# labwiz-module_full_breakout.net
KiCad netlist of a schematic drawn in EAGLE
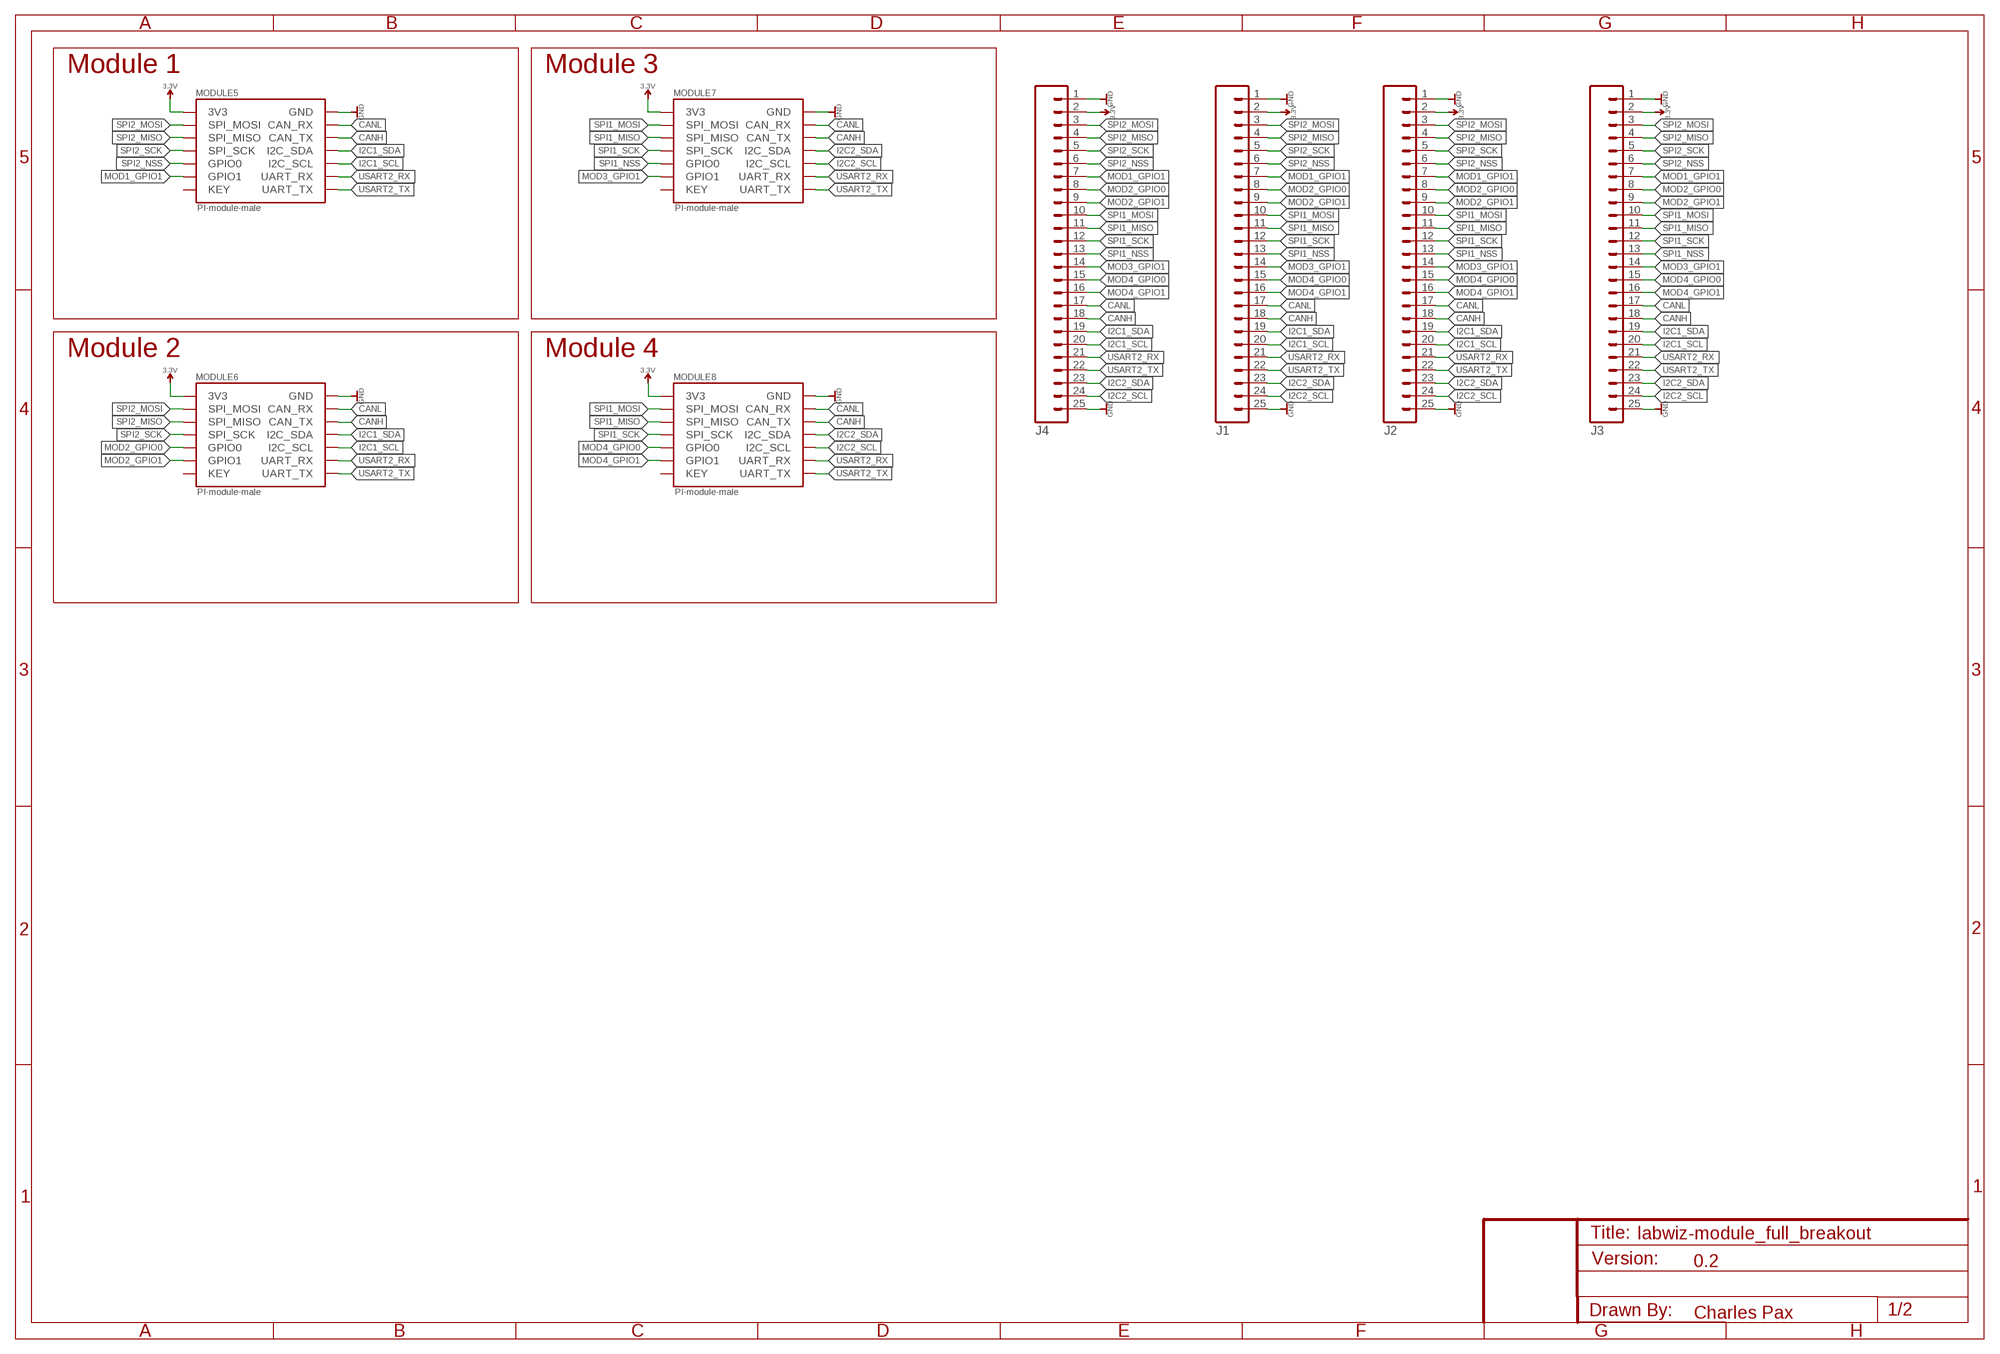
[diagram p0: schematic, sheet 1]

(export (version "E")
  (design (tool "Eeschema 10.0.6"))
  (components
    (comp (ref "J1")
      (value "M25PTH")
      (footprint "eagle-import:1X25")
      (libsource (lib "eagle-import") (part "M25PTH"))
    )
    (comp (ref "J2")
      (value "M25PTH")
      (footprint "eagle-import:1X25")
      (libsource (lib "eagle-import") (part "M25PTH"))
    )
    (comp (ref "J3")
      (value "M25PTH")
      (footprint "eagle-import:1X25")
      (libsource (lib "eagle-import") (part "M25PTH"))
    )
    (comp (ref "J4")
      (value "M25PTH")
      (footprint "eagle-import:1X25")
      (libsource (lib "eagle-import") (part "M25PTH"))
    )
    (comp (ref "MODULE5")
      (value "PI-module-male")
      (footprint "eagle-import:M07X2_2MM_EDGE")
      (fields (field (name "MF") "Pax Instruments") (field (name "MPN") "PIxxxx"))
      (libsource (lib "eagle-import") (part "PAX_MODULE_EDGE_MALE_MODULE"))
    )
    (comp (ref "MODULE6")
      (value "PI-module-male")
      (footprint "eagle-import:M07X2_2MM_EDGE")
      (fields (field (name "MF") "Pax Instruments") (field (name "MPN") "PIxxxx"))
      (libsource (lib "eagle-import") (part "PAX_MODULE_EDGE_MALE_MODULE"))
    )
    (comp (ref "MODULE7")
      (value "PI-module-male")
      (footprint "eagle-import:M07X2_2MM_EDGE")
      (fields (field (name "MF") "Pax Instruments") (field (name "MPN") "PIxxxx"))
      (libsource (lib "eagle-import") (part "PAX_MODULE_EDGE_MALE_MODULE"))
    )
    (comp (ref "MODULE8")
      (value "PI-module-male")
      (footprint "eagle-import:M07X2_2MM_EDGE")
      (fields (field (name "MF") "Pax Instruments") (field (name "MPN") "PIxxxx"))
      (libsource (lib "eagle-import") (part "PAX_MODULE_EDGE_MALE_MODULE"))
    )
  )
  (nets
    (net (code "1") (name "3.3V") (class "Default")
      (node (ref "J1") (pin "2") (pinfunction "2_2") (pintype "passive"))
      (node (ref "J2") (pin "2") (pinfunction "2_2") (pintype "passive"))
      (node (ref "J3") (pin "2") (pinfunction "2_2") (pintype "passive"))
      (node (ref "J4") (pin "2") (pinfunction "2_2") (pintype "passive"))
      (node (ref "MODULE5") (pin "P$13") (pinfunction "3V3_P$13") (pintype "power_in"))
      (node (ref "MODULE6") (pin "P$13") (pinfunction "3V3_P$13") (pintype "power_in"))
      (node (ref "MODULE7") (pin "P$13") (pinfunction "3V3_P$13") (pintype "power_in"))
      (node (ref "MODULE8") (pin "P$13") (pinfunction "3V3_P$13") (pintype "power_in"))
    )
    (net (code "2") (name "CANH") (class "Default")
      (node (ref "J1") (pin "18") (pinfunction "18_18") (pintype "passive"))
      (node (ref "J2") (pin "18") (pinfunction "18_18") (pintype "passive"))
      (node (ref "J3") (pin "18") (pinfunction "18_18") (pintype "passive"))
      (node (ref "J4") (pin "18") (pinfunction "18_18") (pintype "passive"))
      (node (ref "MODULE5") (pin "P$10") (pinfunction "CAN_TX_P$10") (pintype "bidirectional"))
      (node (ref "MODULE6") (pin "P$10") (pinfunction "CAN_TX_P$10") (pintype "bidirectional"))
      (node (ref "MODULE7") (pin "P$10") (pinfunction "CAN_TX_P$10") (pintype "bidirectional"))
      (node (ref "MODULE8") (pin "P$10") (pinfunction "CAN_TX_P$10") (pintype "bidirectional"))
    )
    (net (code "3") (name "CANL") (class "Default")
      (node (ref "J1") (pin "17") (pinfunction "17_17") (pintype "passive"))
      (node (ref "J2") (pin "17") (pinfunction "17_17") (pintype "passive"))
      (node (ref "J3") (pin "17") (pinfunction "17_17") (pintype "passive"))
      (node (ref "J4") (pin "17") (pinfunction "17_17") (pintype "passive"))
      (node (ref "MODULE5") (pin "P$12") (pinfunction "CAN_RX_P$12") (pintype "bidirectional"))
      (node (ref "MODULE6") (pin "P$12") (pinfunction "CAN_RX_P$12") (pintype "bidirectional"))
      (node (ref "MODULE7") (pin "P$12") (pinfunction "CAN_RX_P$12") (pintype "bidirectional"))
      (node (ref "MODULE8") (pin "P$12") (pinfunction "CAN_RX_P$12") (pintype "bidirectional"))
    )
    (net (code "4") (name "GND") (class "Default")
      (node (ref "J1") (pin "1") (pinfunction "1_1") (pintype "passive"))
      (node (ref "J1") (pin "25") (pinfunction "25_25") (pintype "passive"))
      (node (ref "J2") (pin "1") (pinfunction "1_1") (pintype "passive"))
      (node (ref "J2") (pin "25") (pinfunction "25_25") (pintype "passive"))
      (node (ref "J3") (pin "1") (pinfunction "1_1") (pintype "passive"))
      (node (ref "J3") (pin "25") (pinfunction "25_25") (pintype "passive"))
      (node (ref "J4") (pin "1") (pinfunction "1_1") (pintype "passive"))
      (node (ref "J4") (pin "25") (pinfunction "25_25") (pintype "passive"))
      (node (ref "MODULE5") (pin "P$14") (pinfunction "GND_P$14") (pintype "power_in"))
      (node (ref "MODULE6") (pin "P$14") (pinfunction "GND_P$14") (pintype "power_in"))
      (node (ref "MODULE7") (pin "P$14") (pinfunction "GND_P$14") (pintype "power_in"))
      (node (ref "MODULE8") (pin "P$14") (pinfunction "GND_P$14") (pintype "power_in"))
    )
    (net (code "5") (name "I2C1_SCL") (class "Default")
      (node (ref "J1") (pin "20") (pinfunction "20_20") (pintype "passive"))
      (node (ref "J2") (pin "20") (pinfunction "20_20") (pintype "passive"))
      (node (ref "J3") (pin "20") (pinfunction "20_20") (pintype "passive"))
      (node (ref "J4") (pin "20") (pinfunction "20_20") (pintype "passive"))
      (node (ref "MODULE5") (pin "P$6") (pinfunction "I2C_SCL_P$6") (pintype "bidirectional"))
      (node (ref "MODULE6") (pin "P$6") (pinfunction "I2C_SCL_P$6") (pintype "bidirectional"))
    )
    (net (code "6") (name "I2C1_SDA") (class "Default")
      (node (ref "J1") (pin "19") (pinfunction "19_19") (pintype "passive"))
      (node (ref "J2") (pin "19") (pinfunction "19_19") (pintype "passive"))
      (node (ref "J3") (pin "19") (pinfunction "19_19") (pintype "passive"))
      (node (ref "J4") (pin "19") (pinfunction "19_19") (pintype "passive"))
      (node (ref "MODULE5") (pin "P$8") (pinfunction "I2C_SDA_P$8") (pintype "bidirectional"))
      (node (ref "MODULE6") (pin "P$8") (pinfunction "I2C_SDA_P$8") (pintype "bidirectional"))
    )
    (net (code "7") (name "I2C2_SCL") (class "Default")
      (node (ref "J1") (pin "24") (pinfunction "24_24") (pintype "passive"))
      (node (ref "J2") (pin "24") (pinfunction "24_24") (pintype "passive"))
      (node (ref "J3") (pin "24") (pinfunction "24_24") (pintype "passive"))
      (node (ref "J4") (pin "24") (pinfunction "24_24") (pintype "passive"))
      (node (ref "MODULE7") (pin "P$6") (pinfunction "I2C_SCL_P$6") (pintype "bidirectional"))
      (node (ref "MODULE8") (pin "P$6") (pinfunction "I2C_SCL_P$6") (pintype "bidirectional"))
    )
    (net (code "8") (name "I2C2_SDA") (class "Default")
      (node (ref "J1") (pin "23") (pinfunction "23_23") (pintype "passive"))
      (node (ref "J2") (pin "23") (pinfunction "23_23") (pintype "passive"))
      (node (ref "J3") (pin "23") (pinfunction "23_23") (pintype "passive"))
      (node (ref "J4") (pin "23") (pinfunction "23_23") (pintype "passive"))
      (node (ref "MODULE7") (pin "P$8") (pinfunction "I2C_SDA_P$8") (pintype "bidirectional"))
      (node (ref "MODULE8") (pin "P$8") (pinfunction "I2C_SDA_P$8") (pintype "bidirectional"))
    )
    (net (code "9") (name "MOD1_GPIO1") (class "Default")
      (node (ref "J1") (pin "7") (pinfunction "7_7") (pintype "passive"))
      (node (ref "J2") (pin "7") (pinfunction "7_7") (pintype "passive"))
      (node (ref "J3") (pin "7") (pinfunction "7_7") (pintype "passive"))
      (node (ref "J4") (pin "7") (pinfunction "7_7") (pintype "passive"))
      (node (ref "MODULE5") (pin "P$3") (pinfunction "GPIO1_P$3") (pintype "bidirectional"))
    )
    (net (code "10") (name "MOD2_GPIO0") (class "Default")
      (node (ref "J1") (pin "8") (pinfunction "8_8") (pintype "passive"))
      (node (ref "J2") (pin "8") (pinfunction "8_8") (pintype "passive"))
      (node (ref "J3") (pin "8") (pinfunction "8_8") (pintype "passive"))
      (node (ref "J4") (pin "8") (pinfunction "8_8") (pintype "passive"))
      (node (ref "MODULE6") (pin "P$5") (pinfunction "GPIO0_P$5") (pintype "bidirectional"))
    )
    (net (code "11") (name "MOD2_GPIO1") (class "Default")
      (node (ref "J1") (pin "9") (pinfunction "9_9") (pintype "passive"))
      (node (ref "J2") (pin "9") (pinfunction "9_9") (pintype "passive"))
      (node (ref "J3") (pin "9") (pinfunction "9_9") (pintype "passive"))
      (node (ref "J4") (pin "9") (pinfunction "9_9") (pintype "passive"))
      (node (ref "MODULE6") (pin "P$3") (pinfunction "GPIO1_P$3") (pintype "bidirectional"))
    )
    (net (code "12") (name "MOD3_GPIO1") (class "Default")
      (node (ref "J1") (pin "14") (pinfunction "14_14") (pintype "passive"))
      (node (ref "J2") (pin "14") (pinfunction "14_14") (pintype "passive"))
      (node (ref "J3") (pin "14") (pinfunction "14_14") (pintype "passive"))
      (node (ref "J4") (pin "14") (pinfunction "14_14") (pintype "passive"))
      (node (ref "MODULE7") (pin "P$3") (pinfunction "GPIO1_P$3") (pintype "bidirectional"))
    )
    (net (code "13") (name "MOD4_GPIO0") (class "Default")
      (node (ref "J1") (pin "15") (pinfunction "15_15") (pintype "passive"))
      (node (ref "J2") (pin "15") (pinfunction "15_15") (pintype "passive"))
      (node (ref "J3") (pin "15") (pinfunction "15_15") (pintype "passive"))
      (node (ref "J4") (pin "15") (pinfunction "15_15") (pintype "passive"))
      (node (ref "MODULE8") (pin "P$5") (pinfunction "GPIO0_P$5") (pintype "bidirectional"))
    )
    (net (code "14") (name "MOD4_GPIO1") (class "Default")
      (node (ref "J1") (pin "16") (pinfunction "16_16") (pintype "passive"))
      (node (ref "J2") (pin "16") (pinfunction "16_16") (pintype "passive"))
      (node (ref "J3") (pin "16") (pinfunction "16_16") (pintype "passive"))
      (node (ref "J4") (pin "16") (pinfunction "16_16") (pintype "passive"))
      (node (ref "MODULE8") (pin "P$3") (pinfunction "GPIO1_P$3") (pintype "bidirectional"))
    )
    (net (code "15") (name "SPI1_MISO") (class "Default")
      (node (ref "J1") (pin "11") (pinfunction "11_11") (pintype "passive"))
      (node (ref "J2") (pin "11") (pinfunction "11_11") (pintype "passive"))
      (node (ref "J3") (pin "11") (pinfunction "11_11") (pintype "passive"))
      (node (ref "J4") (pin "11") (pinfunction "11_11") (pintype "passive"))
      (node (ref "MODULE7") (pin "P$9") (pinfunction "SPI_MISO_P$9") (pintype "bidirectional"))
      (node (ref "MODULE8") (pin "P$9") (pinfunction "SPI_MISO_P$9") (pintype "bidirectional"))
    )
    (net (code "16") (name "SPI1_MOSI") (class "Default")
      (node (ref "J1") (pin "10") (pinfunction "10_10") (pintype "passive"))
      (node (ref "J2") (pin "10") (pinfunction "10_10") (pintype "passive"))
      (node (ref "J3") (pin "10") (pinfunction "10_10") (pintype "passive"))
      (node (ref "J4") (pin "10") (pinfunction "10_10") (pintype "passive"))
      (node (ref "MODULE7") (pin "P$11") (pinfunction "SPI_MOSI_P$11") (pintype "bidirectional"))
      (node (ref "MODULE8") (pin "P$11") (pinfunction "SPI_MOSI_P$11") (pintype "bidirectional"))
    )
    (net (code "17") (name "SPI1_NSS") (class "Default")
      (node (ref "J1") (pin "13") (pinfunction "13_13") (pintype "passive"))
      (node (ref "J2") (pin "13") (pinfunction "13_13") (pintype "passive"))
      (node (ref "J3") (pin "13") (pinfunction "13_13") (pintype "passive"))
      (node (ref "J4") (pin "13") (pinfunction "13_13") (pintype "passive"))
      (node (ref "MODULE7") (pin "P$5") (pinfunction "GPIO0_P$5") (pintype "bidirectional"))
    )
    (net (code "18") (name "SPI1_SCK") (class "Default")
      (node (ref "J1") (pin "12") (pinfunction "12_12") (pintype "passive"))
      (node (ref "J2") (pin "12") (pinfunction "12_12") (pintype "passive"))
      (node (ref "J3") (pin "12") (pinfunction "12_12") (pintype "passive"))
      (node (ref "J4") (pin "12") (pinfunction "12_12") (pintype "passive"))
      (node (ref "MODULE7") (pin "P$7") (pinfunction "SPI_SCK_P$7") (pintype "bidirectional"))
      (node (ref "MODULE8") (pin "P$7") (pinfunction "SPI_SCK_P$7") (pintype "bidirectional"))
    )
    (net (code "19") (name "SPI2_MISO") (class "Default")
      (node (ref "J1") (pin "4") (pinfunction "4_4") (pintype "passive"))
      (node (ref "J2") (pin "4") (pinfunction "4_4") (pintype "passive"))
      (node (ref "J3") (pin "4") (pinfunction "4_4") (pintype "passive"))
      (node (ref "J4") (pin "4") (pinfunction "4_4") (pintype "passive"))
      (node (ref "MODULE5") (pin "P$9") (pinfunction "SPI_MISO_P$9") (pintype "bidirectional"))
      (node (ref "MODULE6") (pin "P$9") (pinfunction "SPI_MISO_P$9") (pintype "bidirectional"))
    )
    (net (code "20") (name "SPI2_MOSI") (class "Default")
      (node (ref "J1") (pin "3") (pinfunction "3_3") (pintype "passive"))
      (node (ref "J2") (pin "3") (pinfunction "3_3") (pintype "passive"))
      (node (ref "J3") (pin "3") (pinfunction "3_3") (pintype "passive"))
      (node (ref "J4") (pin "3") (pinfunction "3_3") (pintype "passive"))
      (node (ref "MODULE5") (pin "P$11") (pinfunction "SPI_MOSI_P$11") (pintype "bidirectional"))
      (node (ref "MODULE6") (pin "P$11") (pinfunction "SPI_MOSI_P$11") (pintype "bidirectional"))
    )
    (net (code "21") (name "SPI2_NSS") (class "Default")
      (node (ref "J1") (pin "6") (pinfunction "6_6") (pintype "passive"))
      (node (ref "J2") (pin "6") (pinfunction "6_6") (pintype "passive"))
      (node (ref "J3") (pin "6") (pinfunction "6_6") (pintype "passive"))
      (node (ref "J4") (pin "6") (pinfunction "6_6") (pintype "passive"))
      (node (ref "MODULE5") (pin "P$5") (pinfunction "GPIO0_P$5") (pintype "bidirectional"))
    )
    (net (code "22") (name "SPI2_SCK") (class "Default")
      (node (ref "J1") (pin "5") (pinfunction "5_5") (pintype "passive"))
      (node (ref "J2") (pin "5") (pinfunction "5_5") (pintype "passive"))
      (node (ref "J3") (pin "5") (pinfunction "5_5") (pintype "passive"))
      (node (ref "J4") (pin "5") (pinfunction "5_5") (pintype "passive"))
      (node (ref "MODULE5") (pin "P$7") (pinfunction "SPI_SCK_P$7") (pintype "bidirectional"))
      (node (ref "MODULE6") (pin "P$7") (pinfunction "SPI_SCK_P$7") (pintype "bidirectional"))
    )
    (net (code "23") (name "USART2_RX") (class "Default")
      (node (ref "J1") (pin "21") (pinfunction "21_21") (pintype "passive"))
      (node (ref "J2") (pin "21") (pinfunction "21_21") (pintype "passive"))
      (node (ref "J3") (pin "21") (pinfunction "21_21") (pintype "passive"))
      (node (ref "J4") (pin "21") (pinfunction "21_21") (pintype "passive"))
      (node (ref "MODULE5") (pin "P$4") (pinfunction "UART_RX_P$4") (pintype "bidirectional"))
      (node (ref "MODULE6") (pin "P$4") (pinfunction "UART_RX_P$4") (pintype "bidirectional"))
      (node (ref "MODULE7") (pin "P$4") (pinfunction "UART_RX_P$4") (pintype "bidirectional"))
      (node (ref "MODULE8") (pin "P$4") (pinfunction "UART_RX_P$4") (pintype "bidirectional"))
    )
    (net (code "24") (name "USART2_TX") (class "Default")
      (node (ref "J1") (pin "22") (pinfunction "22_22") (pintype "passive"))
      (node (ref "J2") (pin "22") (pinfunction "22_22") (pintype "passive"))
      (node (ref "J3") (pin "22") (pinfunction "22_22") (pintype "passive"))
      (node (ref "J4") (pin "22") (pinfunction "22_22") (pintype "passive"))
      (node (ref "MODULE5") (pin "P$2") (pinfunction "UART_TX_P$2") (pintype "bidirectional"))
      (node (ref "MODULE6") (pin "P$2") (pinfunction "UART_TX_P$2") (pintype "bidirectional"))
      (node (ref "MODULE7") (pin "P$2") (pinfunction "UART_TX_P$2") (pintype "bidirectional"))
      (node (ref "MODULE8") (pin "P$2") (pinfunction "UART_TX_P$2") (pintype "bidirectional"))
    )
    (net (code "25") (name "unconnected-(MODULE5-KEY-PadP$1)") (class "Default")
      (node (ref "MODULE5") (pin "P$1") (pinfunction "KEY_P$1") (pintype "no_connect"))
    )
    (net (code "26") (name "unconnected-(MODULE6-KEY-PadP$1)") (class "Default")
      (node (ref "MODULE6") (pin "P$1") (pinfunction "KEY_P$1") (pintype "no_connect"))
    )
    (net (code "27") (name "unconnected-(MODULE7-KEY-PadP$1)") (class "Default")
      (node (ref "MODULE7") (pin "P$1") (pinfunction "KEY_P$1") (pintype "no_connect"))
    )
    (net (code "28") (name "unconnected-(MODULE8-KEY-PadP$1)") (class "Default")
      (node (ref "MODULE8") (pin "P$1") (pinfunction "KEY_P$1") (pintype "no_connect"))
    )
  )
)
